# schematic.net
KiCad netlist of a schematic drawn in Altium Designer
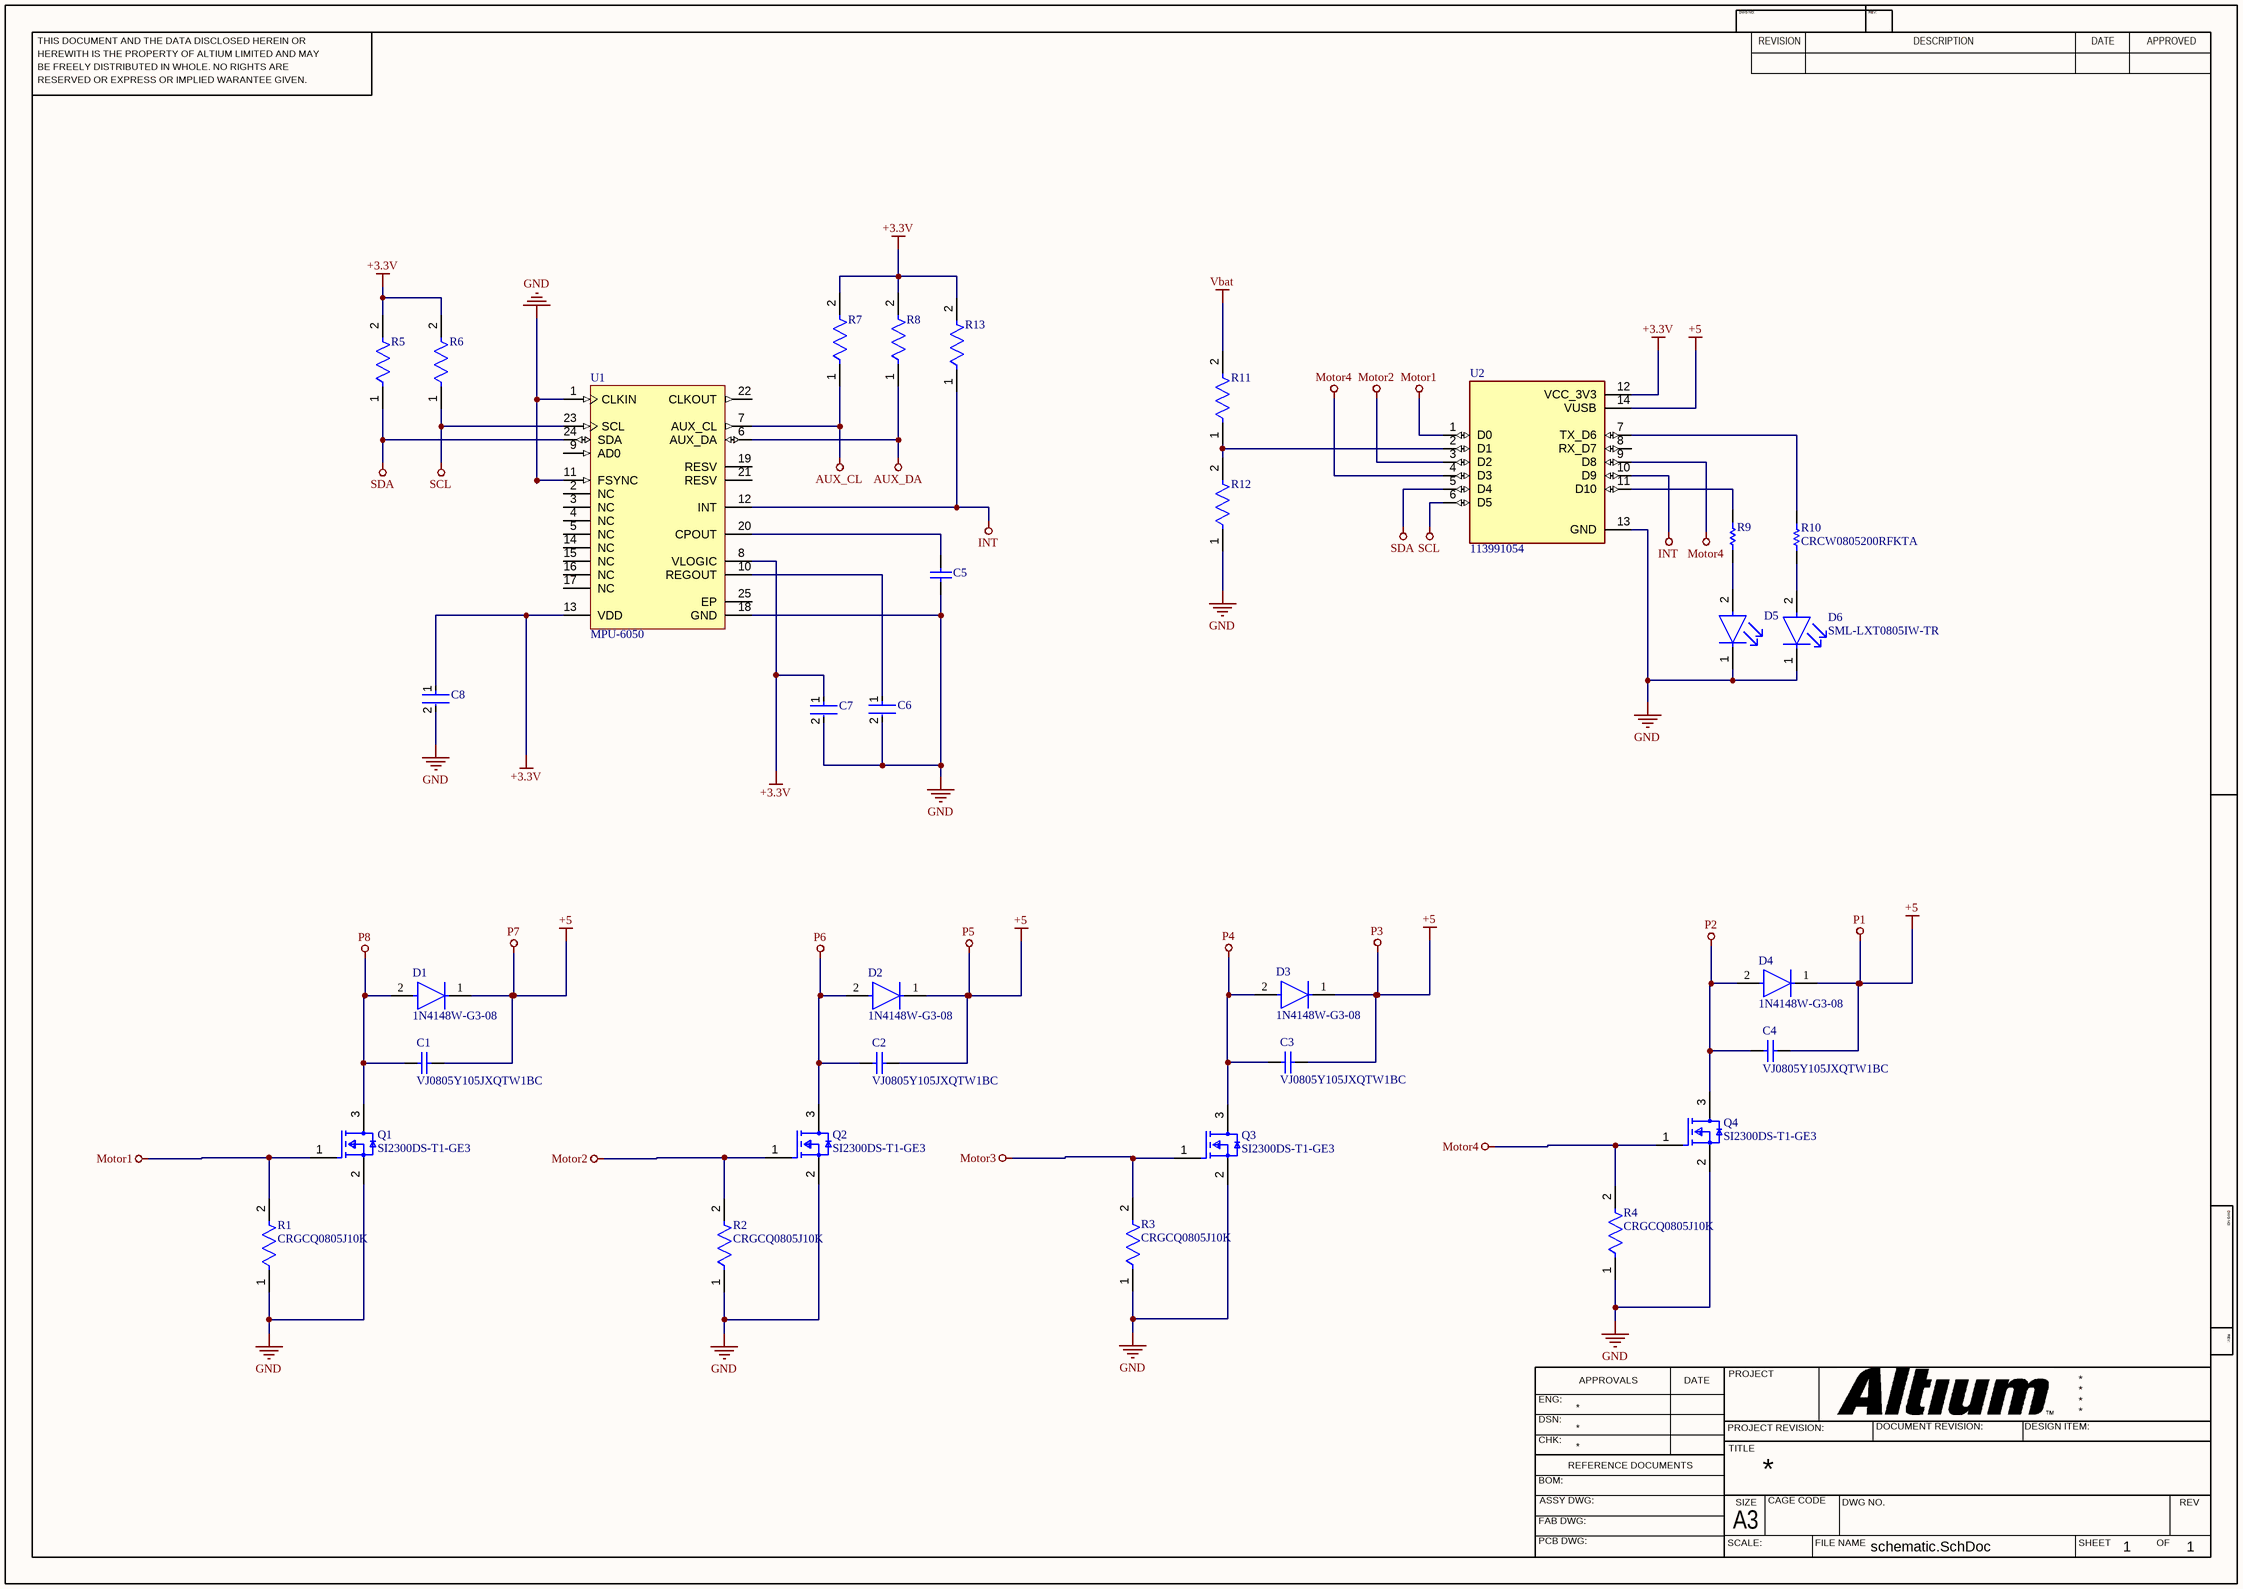
[diagram p0: schematic.SchDoc]

(export (version "E")
  (design (tool "Eeschema 10.0.6"))
  (components
    (comp (ref "C1")
      (value "VJ0805Y105JXQTW1BC")
      (footprint "CAPC2013X145X50LL20T20")
      (fields (field (name "MANUFACTURER") "Vitramon"))
      (libsource (lib "Altium Content Vault") (part "CAP"))
    )
    (comp (ref "C2")
      (value "VJ0805Y105JXQTW1BC")
      (footprint "CAPC2013X145X50LL20T20")
      (fields (field (name "MANUFACTURER") "Vitramon"))
      (libsource (lib "Altium Content Vault") (part "CAP"))
    )
    (comp (ref "C3")
      (value "VJ0805Y105JXQTW1BC")
      (footprint "CAPC2013X145X50LL20T20")
      (fields (field (name "MANUFACTURER") "Vitramon"))
      (libsource (lib "Altium Content Vault") (part "CAP"))
    )
    (comp (ref "C4")
      (value "VJ0805Y105JXQTW1BC")
      (footprint "CAPC2013X145X50LL20T20")
      (fields (field (name "MANUFACTURER") "Vitramon"))
      (libsource (lib "Altium Content Vault") (part "CAP"))
    )
    (comp (ref "C5")
      (value "VJ0805Y221KXAPW1BC")
      (footprint "CAPC2013X145X50NL20T20")
      (fields (field (name "MANUFACTURER") "Vitramon"))
      (libsource (lib "Altium Content Vault") (part "CAP"))
    )
    (comp (ref "C6")
      (value "GRM033R61A104KE15D")
      (footprint "FP-GRM033-0_03-IPC_C")
      (description "Chip Multilayer Ceramic Capacitors for General Purpose, 0201, 0.10uF, X5R, 15%, 10%, 10V")
      (fields (field (name "TOLERANCE") "10%") (field (name "VOLTAGE") "10V"))
      (libsource (lib "Altium Content Vault") (part "b4654b650e69147ec39a6b967a45e02"))
    )
    (comp (ref "C7")
      (value "GRM033R61A104KE15D")
      (footprint "FP-GRM033-0_03-IPC_C")
      (description "Chip Multilayer Ceramic Capacitors for General Purpose, 0201, 0.10uF, X5R, 15%, 10%, 10V")
      (fields (field (name "TOLERANCE") "10%") (field (name "VOLTAGE") "10V"))
      (libsource (lib "Altium Content Vault") (part "b4654b650e69147ec39a6b967a45e02"))
    )
    (comp (ref "C8")
      (value "GRM033R61A104KE15D")
      (footprint "FP-GRM033-0_03-IPC_C")
      (description "Chip Multilayer Ceramic Capacitors for General Purpose, 0201, 0.10uF, X5R, 15%, 10%, 10V")
      (fields (field (name "TOLERANCE") "10%") (field (name "VOLTAGE") "10V"))
      (libsource (lib "Altium Content Vault") (part "b4654b650e69147ec39a6b967a45e02"))
    )
    (comp (ref "D1")
      (value "1N4148W-G3-08")
      (footprint "FP-S8-V-3910_01-001-MFG")
      (description "1N4148W-G3-08 Rectifier Diode, 1 Phase, 1 Element, 0.15A, 100V V(RRM), Silicon")
      (libsource (lib "Altium Content Vault") (part "d7152d700b627762746794eb795d46e"))
    )
    (comp (ref "D2")
      (value "1N4148W-G3-08")
      (footprint "FP-S8-V-3910_01-001-MFG")
      (description "1N4148W-G3-08 Rectifier Diode, 1 Phase, 1 Element, 0.15A, 100V V(RRM), Silicon")
      (libsource (lib "Altium Content Vault") (part "d7152d700b627762746794eb795d46e"))
    )
    (comp (ref "D3")
      (value "1N4148W-G3-08")
      (footprint "FP-S8-V-3910_01-001-MFG")
      (description "1N4148W-G3-08 Rectifier Diode, 1 Phase, 1 Element, 0.15A, 100V V(RRM), Silicon")
      (libsource (lib "Altium Content Vault") (part "d7152d700b627762746794eb795d46e"))
    )
    (comp (ref "D4")
      (value "1N4148W-G3-08")
      (footprint "FP-S8-V-3910_01-001-MFG")
      (description "1N4148W-G3-08 Rectifier Diode, 1 Phase, 1 Element, 0.15A, 100V V(RRM), Silicon")
      (libsource (lib "Altium Content Vault") (part "d7152d700b627762746794eb795d46e"))
    )
    (comp (ref "D5")
      (value "APHCM2012CGCK-F01")
      (footprint "FP-APHCM2012CGCK-F01-MFG")
      (description "LED GREEN CLEAR CHIP SMD")
      (libsource (lib "Altium Content Vault") (part "8706943c75ba83719d021d2fdc84c58"))
    )
    (comp (ref "D6")
      (value "SML-LXT0805IW-TR")
      (footprint "FP-SML-LXT0805IW-TR-MFG")
      (description "LED RED DIFFUSED SMD")
      (libsource (lib "Altium Content Vault") (part "8706943c75ba83719d021d2fdc84c58"))
    )
    (comp (ref "Q1")
      (value "SI2300DS-T1-GE3")
      (footprint "FP-S-03946-MFG")
      (description "MOSFET N-CH 30V 3.6A SOT-23")
      (fields
        (field (name "MANUFACTURER") "Vishay")
        (field (name "OCTOPART") "https://octopart.com/si2300ds-t1-ge3-vishay-44451512")
      )
      (libsource (lib "Altium Content Vault") (part "0a9ea7c96deaaede766a5b531c28de0"))
    )
    (comp (ref "Q2")
      (value "SI2300DS-T1-GE3")
      (footprint "FP-S-03946-MFG")
      (description "MOSFET N-CH 30V 3.6A SOT-23")
      (fields
        (field (name "MANUFACTURER") "Vishay")
        (field (name "OCTOPART") "https://octopart.com/si2300ds-t1-ge3-vishay-44451512")
      )
      (libsource (lib "Altium Content Vault") (part "0a9ea7c96deaaede766a5b531c28de0"))
    )
    (comp (ref "Q3")
      (value "SI2300DS-T1-GE3")
      (footprint "FP-S-03946-MFG")
      (description "MOSFET N-CH 30V 3.6A SOT-23")
      (fields
        (field (name "MANUFACTURER") "Vishay")
        (field (name "OCTOPART") "https://octopart.com/si2300ds-t1-ge3-vishay-44451512")
      )
      (libsource (lib "Altium Content Vault") (part "0a9ea7c96deaaede766a5b531c28de0"))
    )
    (comp (ref "Q4")
      (value "SI2300DS-T1-GE3")
      (footprint "FP-S-03946-MFG")
      (description "MOSFET N-CH 30V 3.6A SOT-23")
      (fields
        (field (name "MANUFACTURER") "Vishay")
        (field (name "OCTOPART") "https://octopart.com/si2300ds-t1-ge3-vishay-44451512")
      )
      (libsource (lib "Altium Content Vault") (part "0a9ea7c96deaaede766a5b531c28de0"))
    )
    (comp (ref "R1")
      (value "CRGCQ0805J10K")
      (footprint "FP-CRGCQ0805-IPC_C")
      (description "CRGCQ 0805 10K 5%")
      (fields (field (name "MANUFACTURER") "TE Connectivity") (field (name "TOLERANCE") "0.05"))
      (libsource (lib "Altium Content Vault") (part "1029c3af85768c4190bb7ad29bc67b5"))
    )
    (comp (ref "R2")
      (value "CRGCQ0805J10K")
      (footprint "FP-CRGCQ0805-IPC_C")
      (description "CRGCQ 0805 10K 5%")
      (fields (field (name "MANUFACTURER") "TE Connectivity") (field (name "TOLERANCE") "0.05"))
      (libsource (lib "Altium Content Vault") (part "1029c3af85768c4190bb7ad29bc67b5"))
    )
    (comp (ref "R3")
      (value "CRGCQ0805J10K")
      (footprint "FP-CRGCQ0805-IPC_C")
      (description "CRGCQ 0805 10K 5%")
      (fields (field (name "MANUFACTURER") "TE Connectivity") (field (name "TOLERANCE") "0.05"))
      (libsource (lib "Altium Content Vault") (part "1029c3af85768c4190bb7ad29bc67b5"))
    )
    (comp (ref "R4")
      (value "CRGCQ0805J10K")
      (footprint "FP-CRGCQ0805-IPC_C")
      (description "CRGCQ 0805 10K 5%")
      (fields (field (name "MANUFACTURER") "TE Connectivity") (field (name "TOLERANCE") "0.05"))
      (libsource (lib "Altium Content Vault") (part "1029c3af85768c4190bb7ad29bc67b5"))
    )
    (comp (ref "R5")
      (value "CRGCQ0805J10K")
      (footprint "FP-CRGCQ0805-IPC_C")
      (description "CRGCQ 0805 10K 5%")
      (fields (field (name "MANUFACTURER") "TE Connectivity") (field (name "TOLERANCE") "0.05"))
      (libsource (lib "Altium Content Vault") (part "1029c3af85768c4190bb7ad29bc67b5"))
    )
    (comp (ref "R6")
      (value "CRGCQ0805J10K")
      (footprint "FP-CRGCQ0805-IPC_C")
      (description "CRGCQ 0805 10K 5%")
      (fields (field (name "MANUFACTURER") "TE Connectivity") (field (name "TOLERANCE") "0.05"))
      (libsource (lib "Altium Content Vault") (part "1029c3af85768c4190bb7ad29bc67b5"))
    )
    (comp (ref "R7")
      (value "CRGCQ0805J10K")
      (footprint "FP-CRGCQ0805-IPC_C")
      (description "CRGCQ 0805 10K 5%")
      (fields (field (name "MANUFACTURER") "TE Connectivity") (field (name "TOLERANCE") "0.05"))
      (libsource (lib "Altium Content Vault") (part "1029c3af85768c4190bb7ad29bc67b5"))
    )
    (comp (ref "R8")
      (value "CRGCQ0805J10K")
      (footprint "FP-CRGCQ0805-IPC_C")
      (description "CRGCQ 0805 10K 5%")
      (fields (field (name "MANUFACTURER") "TE Connectivity") (field (name "TOLERANCE") "0.05"))
      (libsource (lib "Altium Content Vault") (part "1029c3af85768c4190bb7ad29bc67b5"))
    )
    (comp (ref "R9")
      (value "CRCW0805200RFKTA")
      (footprint "RESC2013X50X30NL20T20")
      (fields (field (name "MANUFACTURER") "Vishay Dale"))
      (libsource (lib "Altium Content Vault") (part "RES"))
    )
    (comp (ref "R10")
      (value "CRCW0805200RFKTA")
      (footprint "RESC2013X50X30NL20T20")
      (fields (field (name "MANUFACTURER") "Vishay Dale"))
      (libsource (lib "Altium Content Vault") (part "RES"))
    )
    (comp (ref "R11")
      (value "CRGCQ0805J10K")
      (footprint "FP-CRGCQ0805-IPC_C")
      (description "CRGCQ 0805 10K 5%")
      (fields (field (name "MANUFACTURER") "TE Connectivity") (field (name "TOLERANCE") "0.05"))
      (libsource (lib "Altium Content Vault") (part "1029c3af85768c4190bb7ad29bc67b5"))
    )
    (comp (ref "R12")
      (value "CRGCQ0805J10K")
      (footprint "FP-CRGCQ0805-IPC_C")
      (description "CRGCQ 0805 10K 5%")
      (fields (field (name "MANUFACTURER") "TE Connectivity") (field (name "TOLERANCE") "0.05"))
      (libsource (lib "Altium Content Vault") (part "1029c3af85768c4190bb7ad29bc67b5"))
    )
    (comp (ref "R13")
      (value "CRGCQ0805J10K")
      (footprint "FP-CRGCQ0805-IPC_C")
      (description "CRGCQ 0805 10K 5%")
      (fields (field (name "MANUFACTURER") "TE Connectivity") (field (name "TOLERANCE") "0.05"))
      (libsource (lib "Altium Content Vault") (part "1029c3af85768c4190bb7ad29bc67b5"))
    )
    (comp (ref "U1")
      (value "MPU-6050")
      (footprint "IS-QFN-24_V")
      (fields (field (name "MANUFACTURER") "InvenSense"))
      (libsource (lib "Altium Content Vault") (part "IS-MPU-6050-QFN-24"))
    )
    (comp (ref "U2")
      (value "113991054")
      (footprint "MODULE_113991054")
      (fields (field (name "MF") "Seeed Technology Co., Ltd"))
      (libsource (lib "113991054 (1)") (part "113991054"))
    )
  )
  (nets
    (net (code "1") (name "+3.3V") (class "Default")
      (node (ref "C7") (pin "1") (pinfunction "1_1") (pintype "passive"))
      (node (ref "C8") (pin "1") (pinfunction "1_1") (pintype "passive"))
      (node (ref "R13") (pin "2") (pinfunction "2_2") (pintype "passive"))
      (node (ref "R5") (pin "2") (pinfunction "2_2") (pintype "passive"))
      (node (ref "R6") (pin "2") (pinfunction "2_2") (pintype "passive"))
      (node (ref "R7") (pin "2") (pinfunction "2_2") (pintype "passive"))
      (node (ref "R8") (pin "2") (pinfunction "2_2") (pintype "passive"))
      (node (ref "U1") (pin "13") (pinfunction "VDD_13") (pintype "power_in"))
      (node (ref "U1") (pin "8") (pinfunction "VLOGIC_8") (pintype "power_in"))
      (node (ref "U2") (pin "12") (pinfunction "VCC_3V3_12") (pintype "power_in"))
    )
    (net (code "2") (name "+5") (class "Default")
      (node (ref "C1") (pin "2") (pinfunction "2_2") (pintype "passive"))
      (node (ref "C2") (pin "2") (pinfunction "2_2") (pintype "passive"))
      (node (ref "C3") (pin "2") (pinfunction "2_2") (pintype "passive"))
      (node (ref "C4") (pin "2") (pinfunction "2_2") (pintype "passive"))
      (node (ref "D1") (pin "1") (pinfunction "C_1") (pintype "passive"))
      (node (ref "D2") (pin "1") (pinfunction "C_1") (pintype "passive"))
      (node (ref "D3") (pin "1") (pinfunction "C_1") (pintype "passive"))
      (node (ref "D4") (pin "1") (pinfunction "C_1") (pintype "passive"))
      (node (ref "U2") (pin "14") (pinfunction "VUSB_14") (pintype "power_in"))
    )
    (net (code "3") (name "AUX_CL") (class "Default")
      (node (ref "R7") (pin "1") (pinfunction "1_1") (pintype "passive"))
      (node (ref "U1") (pin "7") (pinfunction "AUX_CL_7") (pintype "output"))
    )
    (net (code "4") (name "AUX_DA") (class "Default")
      (node (ref "R8") (pin "1") (pinfunction "1_1") (pintype "passive"))
      (node (ref "U1") (pin "6") (pinfunction "AUX_DA_6") (pintype "bidirectional"))
    )
    (net (code "5") (name "GND") (class "Default")
      (node (ref "C5") (pin "1") (pinfunction "1_1") (pintype "passive"))
      (node (ref "C6") (pin "2") (pinfunction "2_2") (pintype "passive"))
      (node (ref "C7") (pin "2") (pinfunction "2_2") (pintype "passive"))
      (node (ref "C8") (pin "2") (pinfunction "2_2") (pintype "passive"))
      (node (ref "D5") (pin "1") (pinfunction "C_1") (pintype "passive"))
      (node (ref "D6") (pin "1") (pinfunction "C_1") (pintype "passive"))
      (node (ref "Q1") (pin "2") (pinfunction "S_2") (pintype "passive"))
      (node (ref "Q2") (pin "2") (pinfunction "S_2") (pintype "passive"))
      (node (ref "Q3") (pin "2") (pinfunction "S_2") (pintype "passive"))
      (node (ref "Q4") (pin "2") (pinfunction "S_2") (pintype "passive"))
      (node (ref "R1") (pin "1") (pinfunction "1_1") (pintype "passive"))
      (node (ref "R12") (pin "1") (pinfunction "1_1") (pintype "passive"))
      (node (ref "R2") (pin "1") (pinfunction "1_1") (pintype "passive"))
      (node (ref "R3") (pin "1") (pinfunction "1_1") (pintype "passive"))
      (node (ref "R4") (pin "1") (pinfunction "1_1") (pintype "passive"))
      (node (ref "U1") (pin "1") (pinfunction "CLKIN_1") (pintype "input"))
      (node (ref "U1") (pin "11") (pinfunction "FSYNC_11") (pintype "input"))
      (node (ref "U1") (pin "18") (pinfunction "GND_18") (pintype "power_in"))
      (node (ref "U2") (pin "13") (pinfunction "GND_13") (pintype "power_in"))
    )
    (net (code "6") (name "INT") (class "Default")
      (node (ref "R13") (pin "1") (pinfunction "1_1") (pintype "passive"))
      (node (ref "U1") (pin "12") (pinfunction "INT_12") (pintype "open_collector"))
      (node (ref "U2") (pin "10") (pinfunction "D9_10") (pintype "bidirectional"))
    )
    (net (code "7") (name "Motor1") (class "Default")
      (node (ref "Q1") (pin "1") (pinfunction "G_1") (pintype "passive"))
      (node (ref "R1") (pin "2") (pinfunction "2_2") (pintype "passive"))
      (node (ref "U2") (pin "1") (pinfunction "D0_1") (pintype "bidirectional"))
    )
    (net (code "8") (name "Motor2") (class "Default")
      (node (ref "Q2") (pin "1") (pinfunction "G_1") (pintype "passive"))
      (node (ref "R2") (pin "2") (pinfunction "2_2") (pintype "passive"))
      (node (ref "U2") (pin "3") (pinfunction "D2_3") (pintype "bidirectional"))
    )
    (net (code "9") (name "Motor3") (class "Default")
      (node (ref "Q3") (pin "1") (pinfunction "G_1") (pintype "passive"))
      (node (ref "R3") (pin "2") (pinfunction "2_2") (pintype "passive"))
    )
    (net (code "10") (name "Motor4") (class "Default")
      (node (ref "Q4") (pin "1") (pinfunction "G_1") (pintype "passive"))
      (node (ref "R4") (pin "2") (pinfunction "2_2") (pintype "passive"))
      (node (ref "U2") (pin "4") (pinfunction "D3_4") (pintype "bidirectional"))
      (node (ref "U2") (pin "9") (pinfunction "D8_9") (pintype "bidirectional"))
    )
    (net (code "11") (name "Net-(D5-A)") (class "Default")
      (node (ref "D5") (pin "2") (pinfunction "A_2") (pintype "passive"))
      (node (ref "R9") (pin "1") (pinfunction "1_1") (pintype "passive"))
    )
    (net (code "12") (name "Net-(D6-A)") (class "Default")
      (node (ref "D6") (pin "2") (pinfunction "A_2") (pintype "passive"))
      (node (ref "R10") (pin "1") (pinfunction "1_1") (pintype "passive"))
    )
    (net (code "13") (name "Net-(U1-CPOUT)") (class "Default")
      (node (ref "C5") (pin "2") (pinfunction "2_2") (pintype "passive"))
      (node (ref "U1") (pin "20") (pinfunction "CPOUT_20") (pintype "passive"))
    )
    (net (code "14") (name "Net-(U1-REGOUT)") (class "Default")
      (node (ref "C6") (pin "1") (pinfunction "1_1") (pintype "passive"))
      (node (ref "U1") (pin "10") (pinfunction "REGOUT_10") (pintype "passive"))
    )
    (net (code "15") (name "Net-(U2-D1)") (class "Default")
      (node (ref "R11") (pin "1") (pinfunction "1_1") (pintype "passive"))
      (node (ref "R12") (pin "2") (pinfunction "2_2") (pintype "passive"))
      (node (ref "U2") (pin "2") (pinfunction "D1_2") (pintype "bidirectional"))
    )
    (net (code "16") (name "Net-(U2-D10)") (class "Default")
      (node (ref "R9") (pin "2") (pinfunction "2_2") (pintype "passive"))
      (node (ref "U2") (pin "11") (pinfunction "D10_11") (pintype "bidirectional"))
    )
    (net (code "17") (name "Net-(U2-TX_D6)") (class "Default")
      (node (ref "R10") (pin "2") (pinfunction "2_2") (pintype "passive"))
      (node (ref "U2") (pin "7") (pinfunction "TX_D6_7") (pintype "bidirectional"))
    )
    (net (code "18") (name "P2") (class "Default")
      (node (ref "C4") (pin "1") (pinfunction "1_1") (pintype "passive"))
      (node (ref "D4") (pin "2") (pinfunction "A_2") (pintype "passive"))
      (node (ref "Q4") (pin "3") (pinfunction "D_3") (pintype "passive"))
    )
    (net (code "19") (name "P4") (class "Default")
      (node (ref "C3") (pin "1") (pinfunction "1_1") (pintype "passive"))
      (node (ref "D3") (pin "2") (pinfunction "A_2") (pintype "passive"))
      (node (ref "Q3") (pin "3") (pinfunction "D_3") (pintype "passive"))
    )
    (net (code "20") (name "P6") (class "Default")
      (node (ref "C2") (pin "1") (pinfunction "1_1") (pintype "passive"))
      (node (ref "D2") (pin "2") (pinfunction "A_2") (pintype "passive"))
      (node (ref "Q2") (pin "3") (pinfunction "D_3") (pintype "passive"))
    )
    (net (code "21") (name "P8") (class "Default")
      (node (ref "C1") (pin "1") (pinfunction "1_1") (pintype "passive"))
      (node (ref "D1") (pin "2") (pinfunction "A_2") (pintype "passive"))
      (node (ref "Q1") (pin "3") (pinfunction "D_3") (pintype "passive"))
    )
    (net (code "22") (name "SCL") (class "Default")
      (node (ref "R6") (pin "1") (pinfunction "1_1") (pintype "passive"))
      (node (ref "U1") (pin "23") (pinfunction "SCL_23") (pintype "input"))
      (node (ref "U2") (pin "6") (pinfunction "D5_6") (pintype "bidirectional"))
    )
    (net (code "23") (name "SDA") (class "Default")
      (node (ref "R5") (pin "1") (pinfunction "1_1") (pintype "passive"))
      (node (ref "U1") (pin "24") (pinfunction "SDA_24") (pintype "bidirectional"))
      (node (ref "U2") (pin "5") (pinfunction "D4_5") (pintype "bidirectional"))
    )
    (net (code "24") (name "Vbat") (class "Default")
      (node (ref "R11") (pin "2") (pinfunction "2_2") (pintype "passive"))
    )
    (net (code "25") (name "unconnected-(U1-AD0-Pad9)") (class "Default")
      (node (ref "U1") (pin "9") (pinfunction "AD0_9") (pintype "input"))
    )
    (net (code "26") (name "unconnected-(U1-CLKOUT-Pad22)") (class "Default")
      (node (ref "U1") (pin "22") (pinfunction "CLKOUT_22") (pintype "output"))
    )
    (net (code "27") (name "unconnected-(U1-EP-Pad25)") (class "Default")
      (node (ref "U1") (pin "25") (pinfunction "EP_25") (pintype "power_in"))
    )
    (net (code "28") (name "unconnected-(U1-NC-Pad2)") (class "Default")
      (node (ref "U1") (pin "2") (pinfunction "NC_2") (pintype "passive"))
    )
    (net (code "29") (name "unconnected-(U1-NC-Pad3)") (class "Default")
      (node (ref "U1") (pin "3") (pinfunction "NC_3") (pintype "passive"))
    )
    (net (code "30") (name "unconnected-(U1-NC-Pad4)") (class "Default")
      (node (ref "U1") (pin "4") (pinfunction "NC_4") (pintype "passive"))
    )
    (net (code "31") (name "unconnected-(U1-NC-Pad5)") (class "Default")
      (node (ref "U1") (pin "5") (pinfunction "NC_5") (pintype "passive"))
    )
    (net (code "32") (name "unconnected-(U1-NC-Pad14)") (class "Default")
      (node (ref "U1") (pin "14") (pinfunction "NC_14") (pintype "passive"))
    )
    (net (code "33") (name "unconnected-(U1-NC-Pad15)") (class "Default")
      (node (ref "U1") (pin "15") (pinfunction "NC_15") (pintype "passive"))
    )
    (net (code "34") (name "unconnected-(U1-NC-Pad16)") (class "Default")
      (node (ref "U1") (pin "16") (pinfunction "NC_16") (pintype "passive"))
    )
    (net (code "35") (name "unconnected-(U1-NC-Pad17)") (class "Default")
      (node (ref "U1") (pin "17") (pinfunction "NC_17") (pintype "passive"))
    )
    (net (code "36") (name "unconnected-(U1-RESV-Pad19)") (class "Default")
      (node (ref "U1") (pin "19") (pinfunction "RESV_19") (pintype "passive"))
    )
    (net (code "37") (name "unconnected-(U1-RESV-Pad21)") (class "Default")
      (node (ref "U1") (pin "21") (pinfunction "RESV_21") (pintype "passive"))
    )
    (net (code "38") (name "unconnected-(U2-RX_D7-Pad8)") (class "Default")
      (node (ref "U2") (pin "8") (pinfunction "RX_D7_8") (pintype "bidirectional"))
    )
  )
)
